# ai_aerea.net
KiCad netlist of a schematic drawn in EAGLE
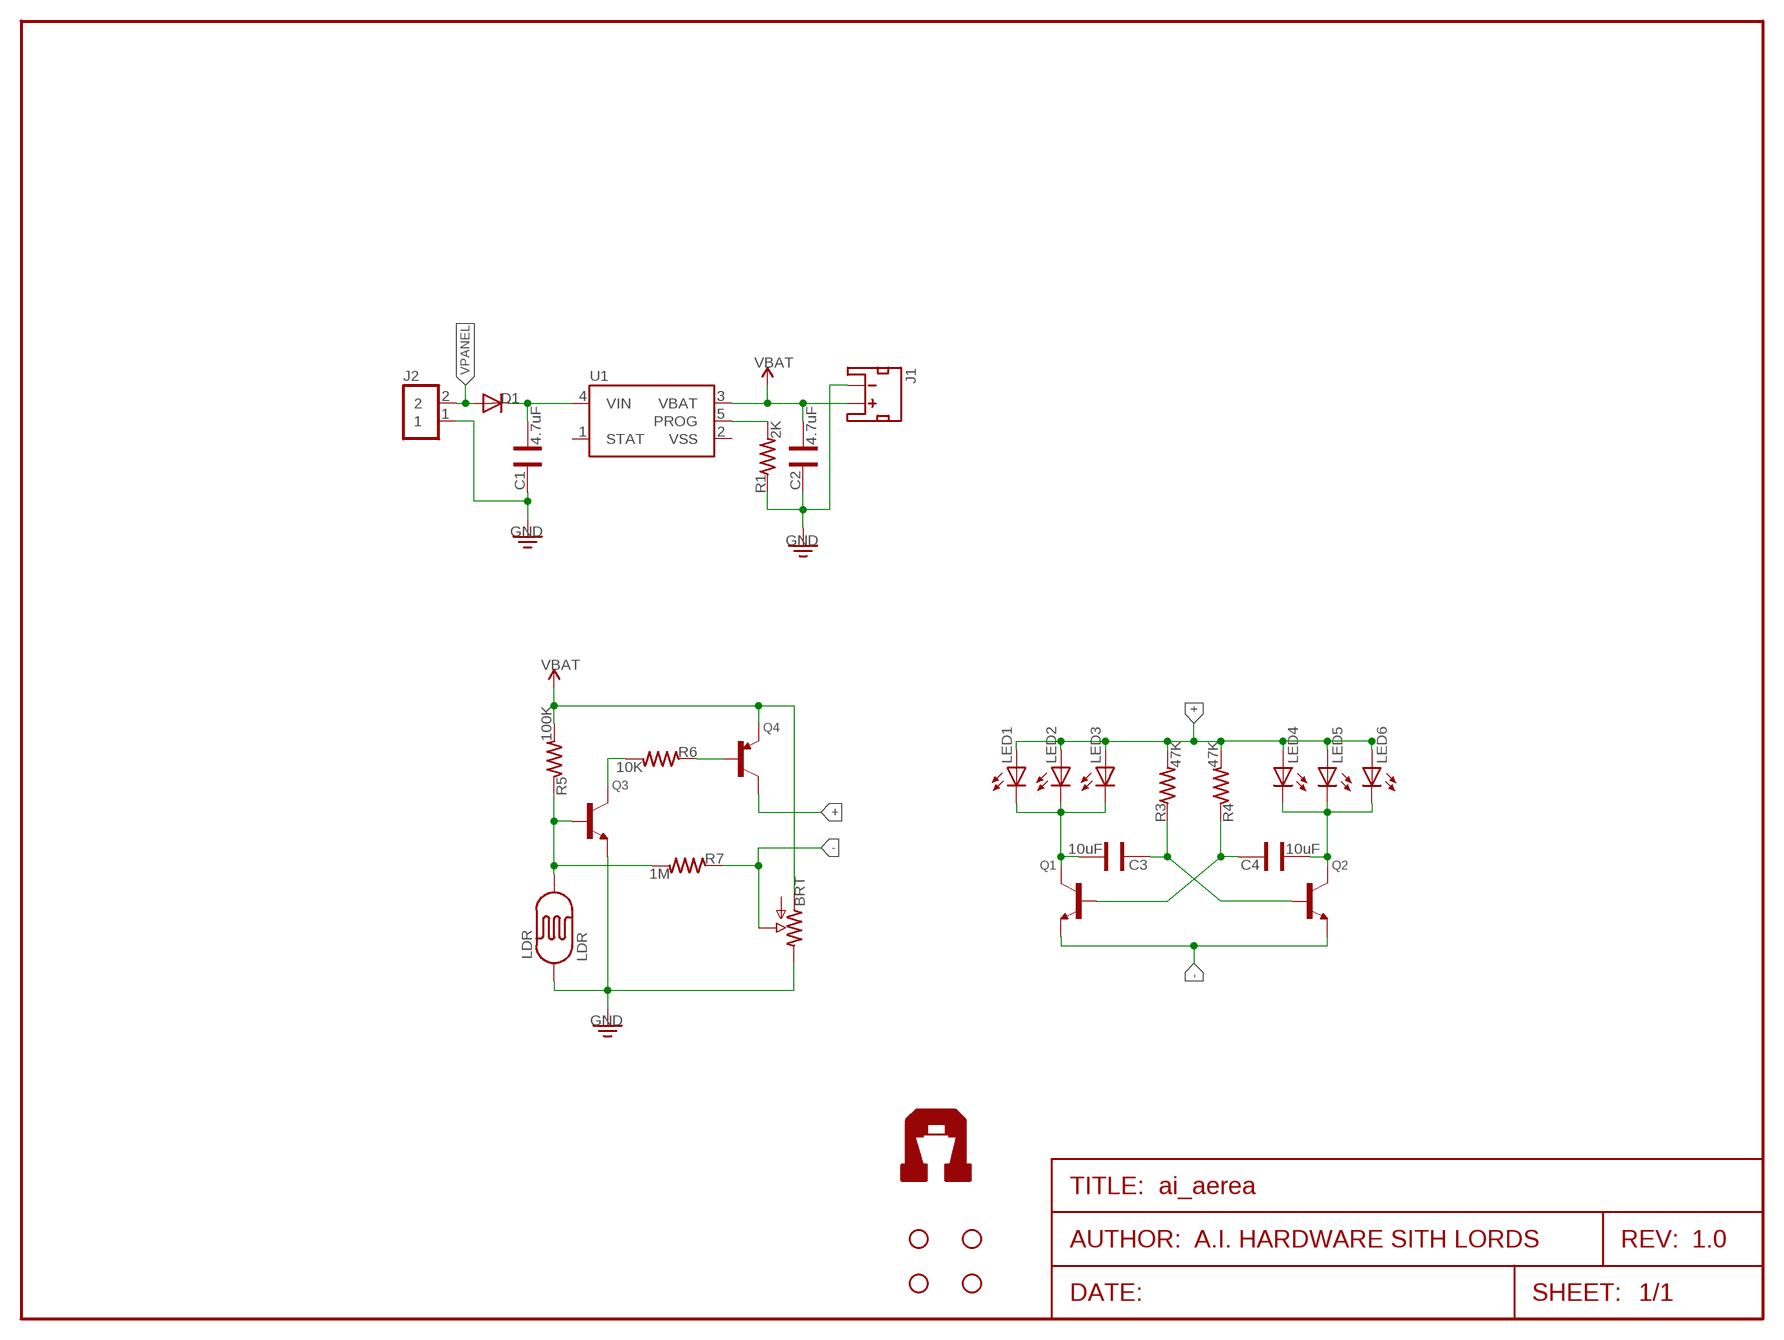
[diagram p0: schematic, sheet 1]

(export (version "E")
  (design (tool "Eeschema 10.0.6"))
  (components
    (comp (ref "BRT")
      (value "POT05X05")
      (footprint "eagle-import:POT-05X05")
      (libsource (lib "eagle-import") (part "POT05X05"))
    )
    (comp (ref "C1")
      (value "4.7uF")
      (footprint "eagle-import:CAP-025X050")
      (libsource (lib "eagle-import") (part "CAP025X050"))
    )
    (comp (ref "C2")
      (value "4.7uF")
      (footprint "eagle-import:CAP-025X050")
      (libsource (lib "eagle-import") (part "CAP025X050"))
    )
    (comp (ref "C3")
      (value "10uF")
      (footprint "eagle-import:CAP-025X050")
      (libsource (lib "eagle-import") (part "CAP025X050"))
    )
    (comp (ref "C4")
      (value "10uF")
      (footprint "eagle-import:CAP-025X050")
      (libsource (lib "eagle-import") (part "CAP025X050"))
    )
    (comp (ref "D1")
      (value "DIODETH-1N914")
      (footprint "eagle-import:TH-1N914")
      (libsource (lib "eagle-import") (part "DIODETH-1N914"))
    )
    (comp (ref "J1")
      (value "JST-2-MALE")
      (footprint "eagle-import:JST-2-SMD")
      (libsource (lib "eagle-import") (part "JST-2-MALE"))
    )
    (comp (ref "J2")
      (value "1X02ST")
      (footprint "eagle-import:1X02-ST")
      (libsource (lib "eagle-import") (part "1X02ST"))
    )
    (comp (ref "LDR")
      (value "LDR-PTH")
      (footprint "eagle-import:LDR")
      (libsource (lib "eagle-import") (part "LDR-PTH"))
    )
    (comp (ref "LED1")
      (value "LED5MM")
      (footprint "eagle-import:LED-5MM")
      (libsource (lib "eagle-import") (part "LED5MM"))
    )
    (comp (ref "LED2")
      (value "LED5MM")
      (footprint "eagle-import:LED-5MM")
      (libsource (lib "eagle-import") (part "LED5MM"))
    )
    (comp (ref "LED3")
      (value "LED5MM")
      (footprint "eagle-import:LED-5MM")
      (libsource (lib "eagle-import") (part "LED5MM"))
    )
    (comp (ref "LED4")
      (value "LED5MM")
      (footprint "eagle-import:LED-5MM")
      (libsource (lib "eagle-import") (part "LED5MM"))
    )
    (comp (ref "LED5")
      (value "LED5MM")
      (footprint "eagle-import:LED-5MM")
      (libsource (lib "eagle-import") (part "LED5MM"))
    )
    (comp (ref "LED6")
      (value "LED5MM")
      (footprint "eagle-import:LED-5MM")
      (libsource (lib "eagle-import") (part "LED5MM"))
    )
    (comp (ref "Q1")
      (value "TRANSISTOR-NPN")
      (footprint "eagle-import:TO-92-NPN")
      (libsource (lib "eagle-import") (part "TRANSISTOR-NPN"))
    )
    (comp (ref "Q2")
      (value "TRANSISTOR-NPN")
      (footprint "eagle-import:TO-92-NPN")
      (libsource (lib "eagle-import") (part "TRANSISTOR-NPN"))
    )
    (comp (ref "Q3")
      (value "TRANSISTOR-NPN")
      (footprint "eagle-import:TO-92-NPN")
      (libsource (lib "eagle-import") (part "TRANSISTOR-NPN"))
    )
    (comp (ref "Q4")
      (value "TRANSISTOR-PNP")
      (footprint "eagle-import:TO-92-PNP")
      (libsource (lib "eagle-import") (part "TRANSISTOR-PNP"))
    )
    (comp (ref "R1")
      (value "2K")
      (footprint "eagle-import:RES-AXIAL-0.4")
      (libsource (lib "eagle-import") (part "RESAXIAL-0.4"))
    )
    (comp (ref "R3")
      (value "47K")
      (footprint "eagle-import:RES-AXIAL-0.4")
      (libsource (lib "eagle-import") (part "RESAXIAL-0.4"))
    )
    (comp (ref "R4")
      (value "47K")
      (footprint "eagle-import:RES-AXIAL-0.4")
      (libsource (lib "eagle-import") (part "RESAXIAL-0.4"))
    )
    (comp (ref "R5")
      (value "100K")
      (footprint "eagle-import:RES-AXIAL-0.4")
      (libsource (lib "eagle-import") (part "RESAXIAL-0.4"))
    )
    (comp (ref "R6")
      (value "10K")
      (footprint "eagle-import:RES-AXIAL-0.4")
      (libsource (lib "eagle-import") (part "RESAXIAL-0.4"))
    )
    (comp (ref "R7")
      (value "1M")
      (footprint "eagle-import:RES-AXIAL-0.4")
      (libsource (lib "eagle-import") (part "RESAXIAL-0.4"))
    )
    (comp (ref "STANDOFF1")
      (value "STAND-OFF")
      (footprint "eagle-import:STAND-OFF")
      (libsource (lib "eagle-import") (part "STAND-OFF"))
    )
    (comp (ref "STANDOFF2")
      (value "STAND-OFF")
      (footprint "eagle-import:STAND-OFF")
      (libsource (lib "eagle-import") (part "STAND-OFF"))
    )
    (comp (ref "STANDOFF3")
      (value "STAND-OFF")
      (footprint "eagle-import:STAND-OFF")
      (libsource (lib "eagle-import") (part "STAND-OFF"))
    )
    (comp (ref "STANDOFF4")
      (value "STAND-OFF")
      (footprint "eagle-import:STAND-OFF")
      (libsource (lib "eagle-import") (part "STAND-OFF"))
    )
    (comp (ref "U$4")
      (value "AI-LOGOM")
      (footprint "eagle-import:AI-LOGO-M")
      (libsource (lib "eagle-import") (part "AI-LOGOM"))
    )
    (comp (ref "U1")
      (value "MCP73831")
      (footprint "eagle-import:SOT23-5")
      (libsource (lib "eagle-import") (part "MCP73831"))
    )
  )
  (nets
    (net (code "1") (name "+") (class "Default")
      (node (ref "LED1") (pin "A") (pinfunction "A_A") (pintype "passive"))
      (node (ref "LED2") (pin "A") (pinfunction "A_A") (pintype "passive"))
      (node (ref "LED3") (pin "A") (pinfunction "A_A") (pintype "passive"))
      (node (ref "LED4") (pin "A") (pinfunction "A_A") (pintype "passive"))
      (node (ref "LED5") (pin "A") (pinfunction "A_A") (pintype "passive"))
      (node (ref "LED6") (pin "A") (pinfunction "A_A") (pintype "passive"))
      (node (ref "Q4") (pin "1") (pinfunction "C_1") (pintype "passive"))
      (node (ref "R3") (pin "P$2") (pinfunction "2_P$2") (pintype "passive"))
      (node (ref "R4") (pin "P$2") (pinfunction "2_P$2") (pintype "passive"))
    )
    (net (code "2") (name "-") (class "Default")
      (node (ref "BRT") (pin "2") (pinfunction "S_2") (pintype "passive"))
      (node (ref "Q1") (pin "1") (pinfunction "E_1") (pintype "passive"))
      (node (ref "Q2") (pin "1") (pinfunction "E_1") (pintype "passive"))
      (node (ref "R7") (pin "P$1") (pinfunction "1_P$1") (pintype "passive"))
    )
    (net (code "3") (name "/VSS") (class "Default")
      (node (ref "U1") (pin "2") (pinfunction "VSS_2") (pintype "power_in"))
    )
    (net (code "4") (name "GND") (class "Default")
      (node (ref "BRT") (pin "1") (pinfunction "E_1") (pintype "passive"))
      (node (ref "C1") (pin "2") (pinfunction "2_2") (pintype "passive"))
      (node (ref "C2") (pin "2") (pinfunction "2_2") (pintype "passive"))
      (node (ref "J1") (pin "2") (pinfunction "-_2") (pintype "power_in"))
      (node (ref "J2") (pin "1") (pinfunction "1_1") (pintype "bidirectional"))
      (node (ref "LDR") (pin "1") (pinfunction "P$1_1") (pintype "bidirectional"))
      (node (ref "Q3") (pin "1") (pinfunction "E_1") (pintype "passive"))
      (node (ref "R1") (pin "P$1") (pinfunction "1_P$1") (pintype "passive"))
    )
    (net (code "5") (name "Net-(LDR-P$2)") (class "Default")
      (node (ref "LDR") (pin "2") (pinfunction "P$2_2") (pintype "bidirectional"))
      (node (ref "Q3") (pin "2") (pinfunction "B_2") (pintype "passive"))
      (node (ref "R5") (pin "P$1") (pinfunction "1_P$1") (pintype "passive"))
      (node (ref "R7") (pin "P$2") (pinfunction "2_P$2") (pintype "passive"))
    )
    (net (code "6") (name "Net-(Q1-B)") (class "Default")
      (node (ref "C4") (pin "2") (pinfunction "2_2") (pintype "passive"))
      (node (ref "Q1") (pin "2") (pinfunction "B_2") (pintype "passive"))
      (node (ref "R4") (pin "P$1") (pinfunction "1_P$1") (pintype "passive"))
    )
    (net (code "7") (name "Net-(Q1-C)") (class "Default")
      (node (ref "C3") (pin "1") (pinfunction "1_1") (pintype "passive"))
      (node (ref "LED1") (pin "C") (pinfunction "C_C") (pintype "passive"))
      (node (ref "LED2") (pin "C") (pinfunction "C_C") (pintype "passive"))
      (node (ref "LED3") (pin "C") (pinfunction "C_C") (pintype "passive"))
      (node (ref "Q1") (pin "3") (pinfunction "C_3") (pintype "passive"))
    )
    (net (code "8") (name "Net-(Q2-B)") (class "Default")
      (node (ref "C3") (pin "2") (pinfunction "2_2") (pintype "passive"))
      (node (ref "Q2") (pin "2") (pinfunction "B_2") (pintype "passive"))
      (node (ref "R3") (pin "P$1") (pinfunction "1_P$1") (pintype "passive"))
    )
    (net (code "9") (name "Net-(Q2-C)") (class "Default")
      (node (ref "C4") (pin "1") (pinfunction "1_1") (pintype "passive"))
      (node (ref "LED4") (pin "C") (pinfunction "C_C") (pintype "passive"))
      (node (ref "LED5") (pin "C") (pinfunction "C_C") (pintype "passive"))
      (node (ref "LED6") (pin "C") (pinfunction "C_C") (pintype "passive"))
      (node (ref "Q2") (pin "3") (pinfunction "C_3") (pintype "passive"))
    )
    (net (code "10") (name "Net-(Q3-C)") (class "Default")
      (node (ref "Q3") (pin "3") (pinfunction "C_3") (pintype "passive"))
      (node (ref "R6") (pin "P$2") (pinfunction "2_P$2") (pintype "passive"))
    )
    (net (code "11") (name "Net-(Q4-B)") (class "Default")
      (node (ref "Q4") (pin "2") (pinfunction "B_2") (pintype "passive"))
      (node (ref "R6") (pin "P$1") (pinfunction "1_P$1") (pintype "passive"))
    )
    (net (code "12") (name "Net-(R1-2)") (class "Default")
      (node (ref "R1") (pin "P$2") (pinfunction "2_P$2") (pintype "passive"))
      (node (ref "U1") (pin "5") (pinfunction "PROG_5") (pintype "input"))
    )
    (net (code "13") (name "Net-(U1-VIN)") (class "Default")
      (node (ref "C1") (pin "1") (pinfunction "1_1") (pintype "passive"))
      (node (ref "D1") (pin "C") (pinfunction "C_C") (pintype "passive"))
      (node (ref "U1") (pin "4") (pinfunction "VIN_4") (pintype "power_in"))
    )
    (net (code "14") (name "VBAT") (class "Default")
      (node (ref "BRT") (pin "3") (pinfunction "A_3") (pintype "passive"))
      (node (ref "C2") (pin "1") (pinfunction "1_1") (pintype "passive"))
      (node (ref "J1") (pin "1") (pinfunction "+_1") (pintype "power_in"))
      (node (ref "Q4") (pin "3") (pinfunction "E_3") (pintype "passive"))
      (node (ref "R5") (pin "P$2") (pinfunction "2_P$2") (pintype "passive"))
      (node (ref "U1") (pin "3") (pinfunction "VBAT_3") (pintype "power_in"))
    )
    (net (code "15") (name "VPANEL") (class "Default")
      (node (ref "D1") (pin "A") (pinfunction "A_A") (pintype "passive"))
      (node (ref "J2") (pin "2") (pinfunction "2_2") (pintype "bidirectional"))
    )
    (net (code "16") (name "unconnected-(U1-STAT-Pad1)") (class "Default")
      (node (ref "U1") (pin "1") (pinfunction "STAT_1") (pintype "output"))
    )
  )
)
